# cococartridge.net
KiCad netlist of a schematic drawn in EAGLE
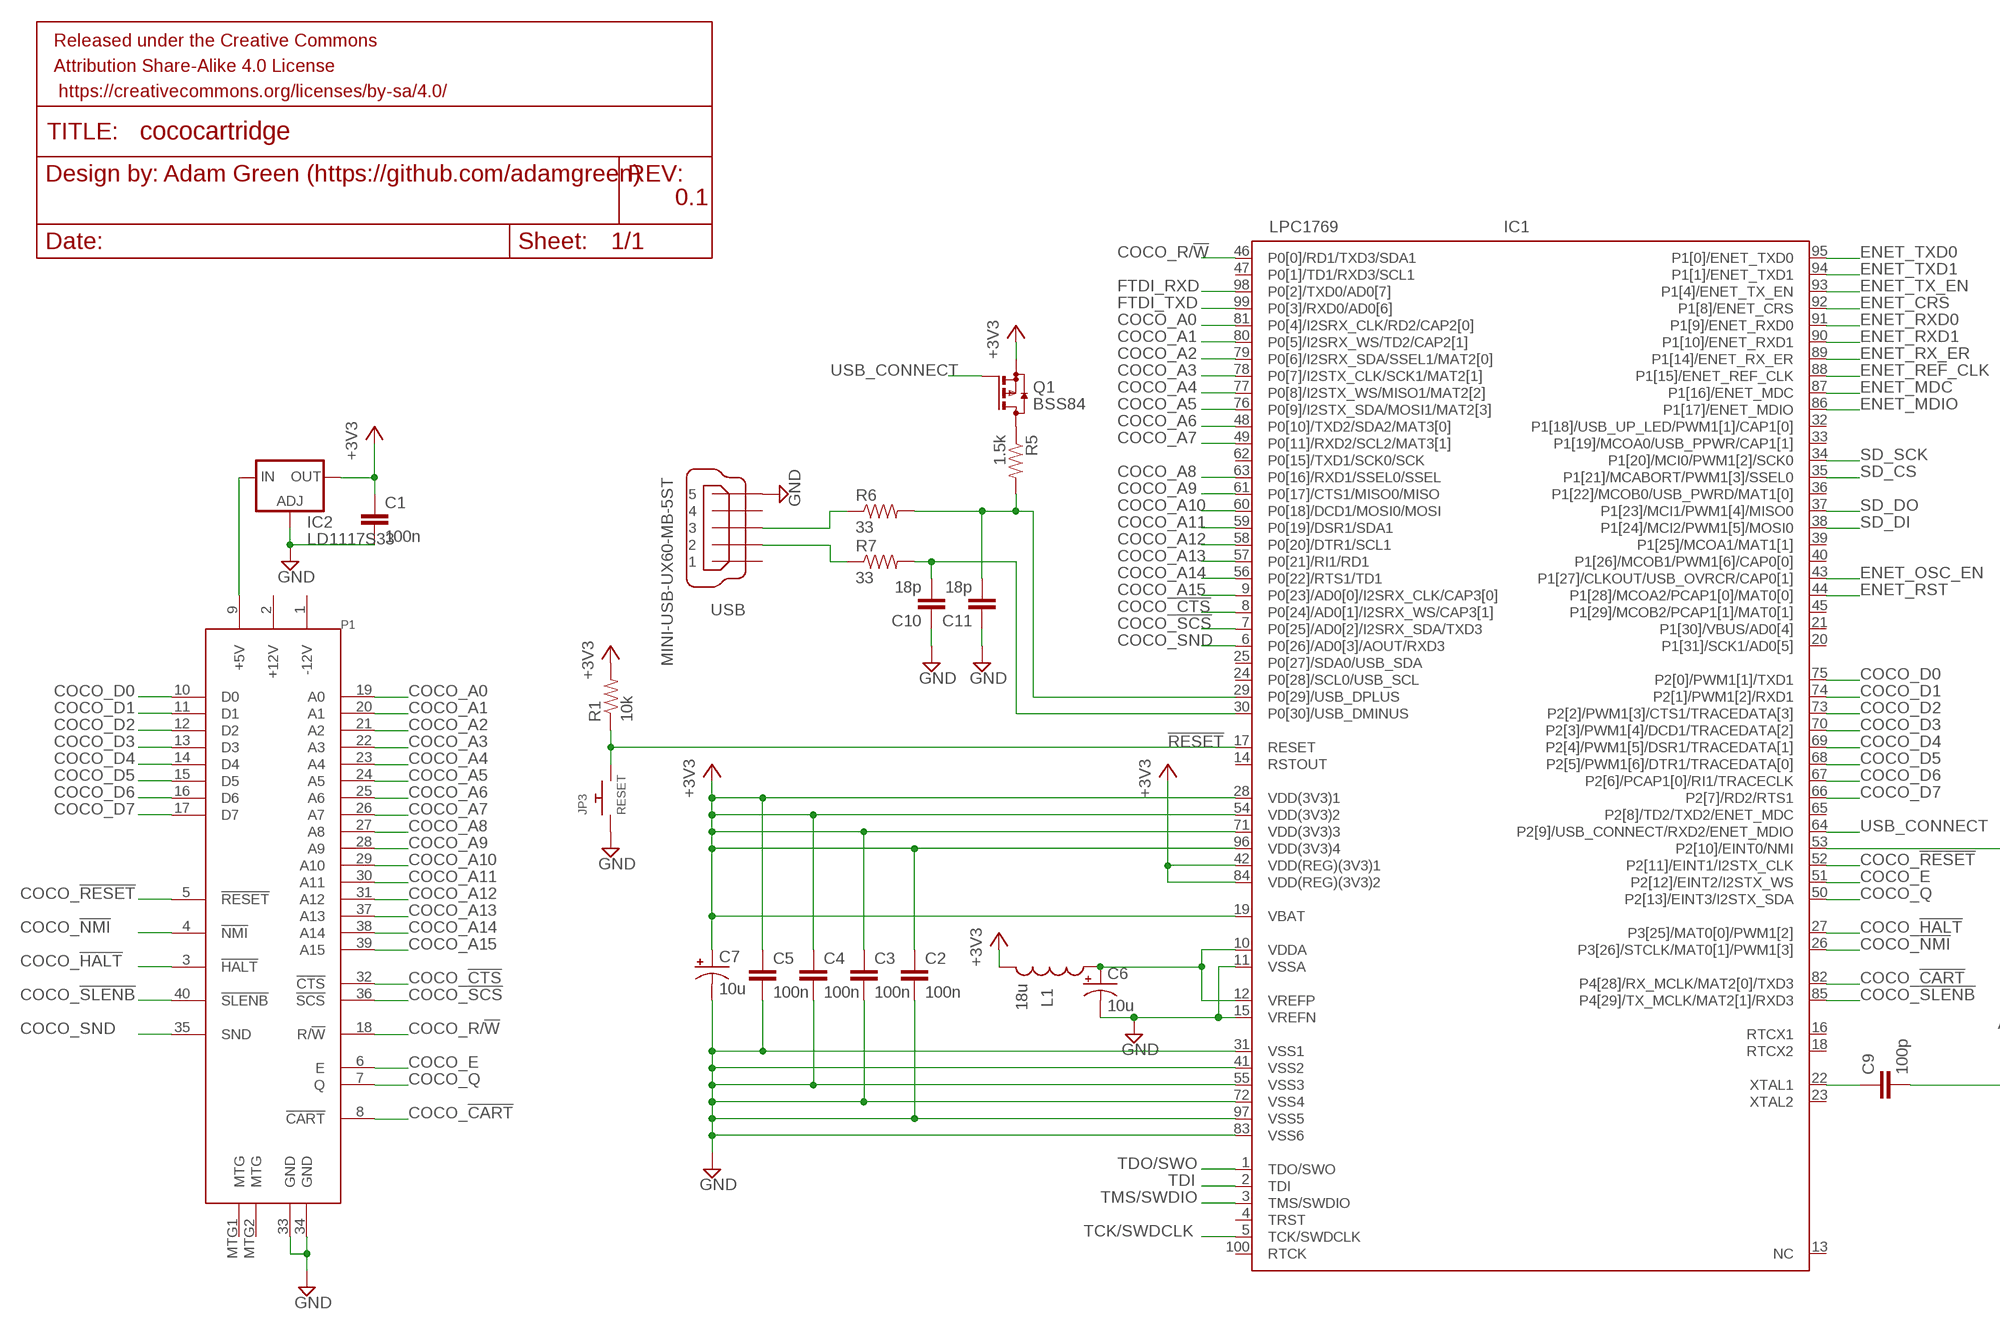
[diagram p0: schematic, sheet 1, part 1 of 2]
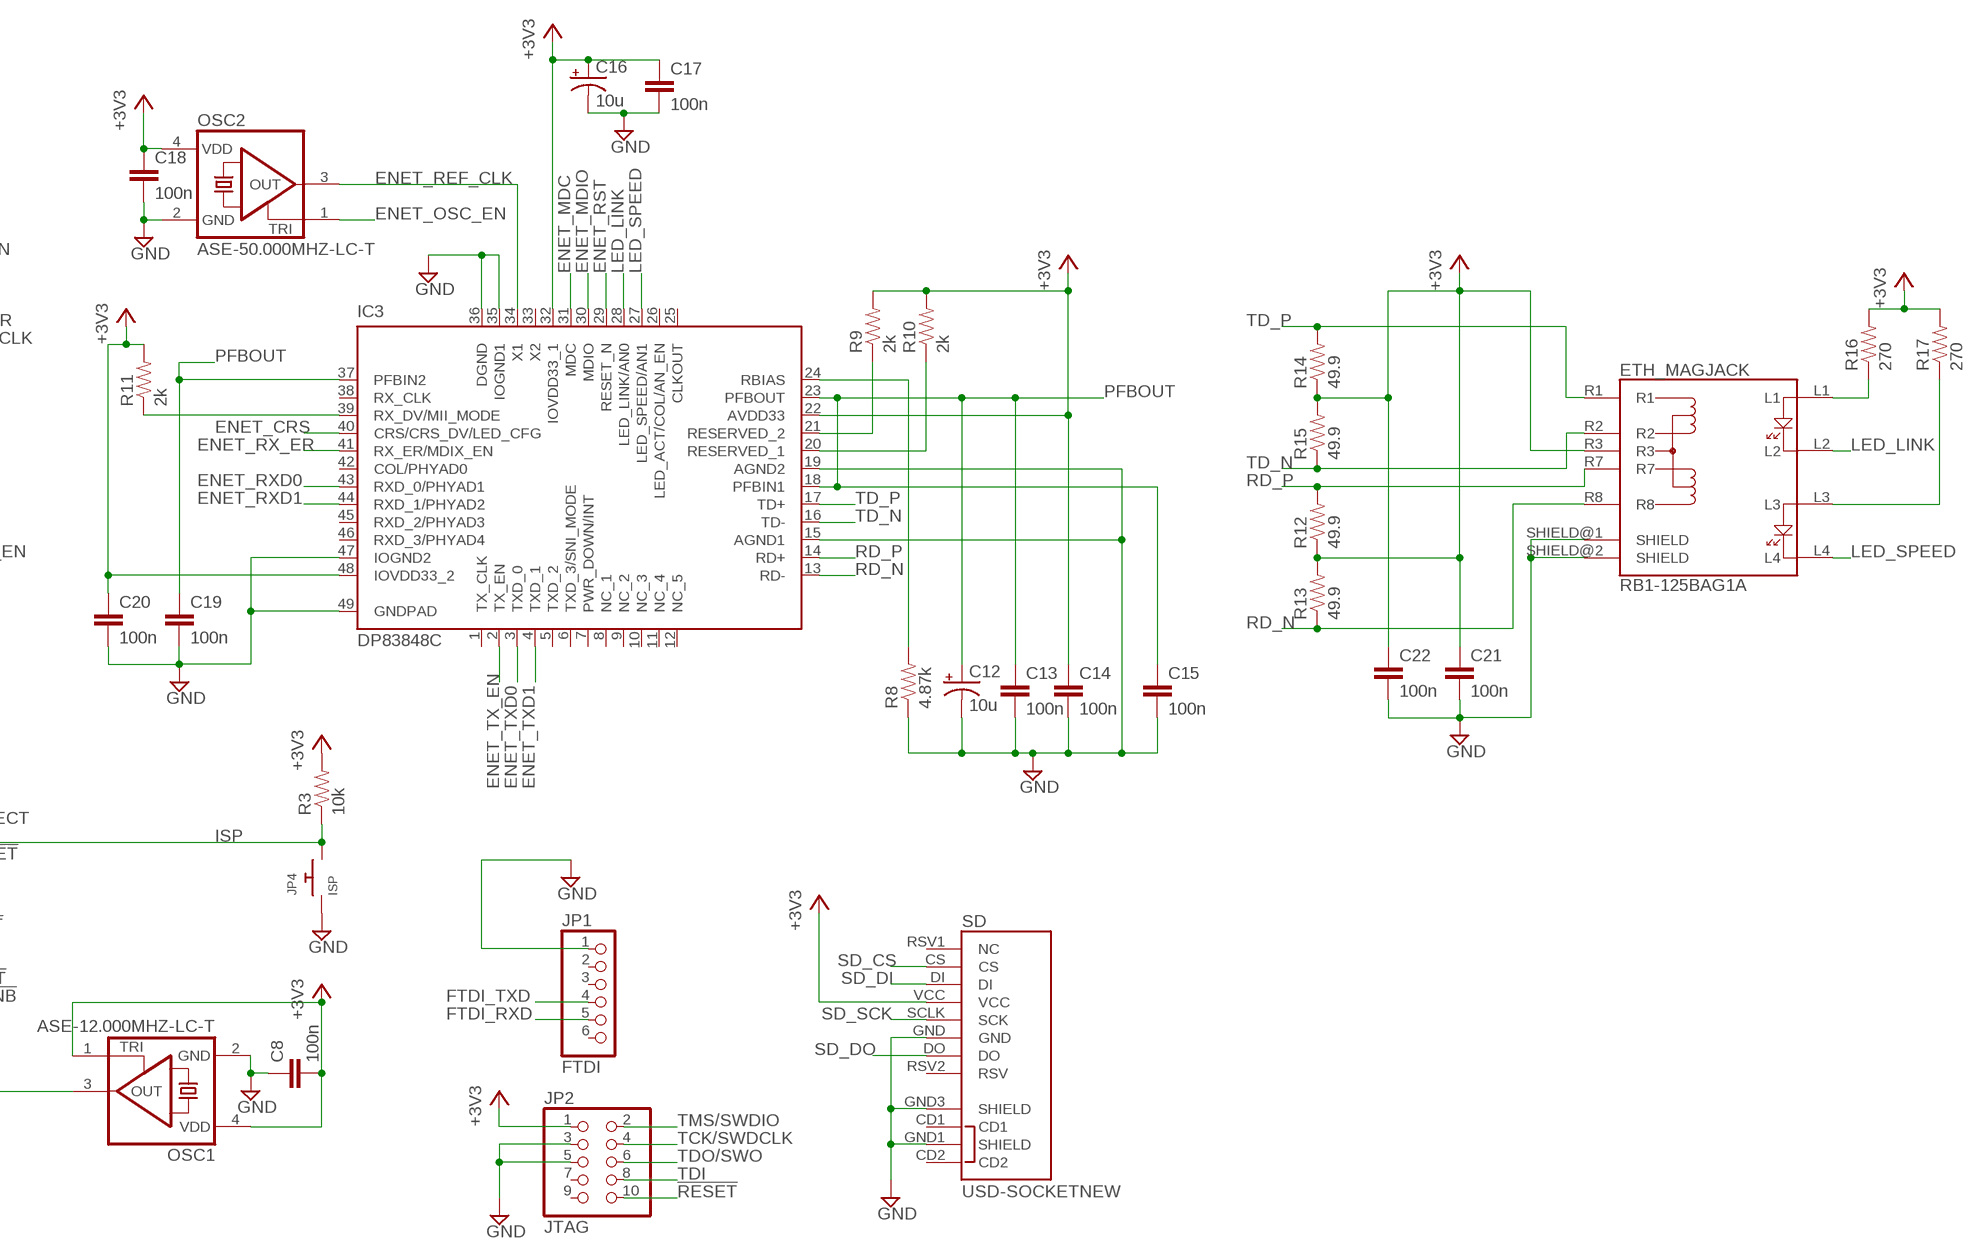
[diagram p1: schematic, sheet 1, part 2 of 2]

(export (version "E")
  (design (tool "Eeschema 10.0.6"))
  (components
    (comp (ref "C1")
      (value "100n")
      (footprint "eagle-import:0805")
      (libsource (lib "eagle-import") (part "CAP0805"))
    )
    (comp (ref "C2")
      (value "100n")
      (footprint "eagle-import:0805")
      (libsource (lib "eagle-import") (part "CAP0805"))
    )
    (comp (ref "C3")
      (value "100n")
      (footprint "eagle-import:0805")
      (libsource (lib "eagle-import") (part "CAP0805"))
    )
    (comp (ref "C4")
      (value "100n")
      (footprint "eagle-import:0805")
      (libsource (lib "eagle-import") (part "CAP0805"))
    )
    (comp (ref "C5")
      (value "100n")
      (footprint "eagle-import:0805")
      (libsource (lib "eagle-import") (part "CAP0805"))
    )
    (comp (ref "C6")
      (value "10u")
      (footprint "eagle-import:EIA3216")
      (libsource (lib "eagle-import") (part "CAP_POL1206"))
    )
    (comp (ref "C7")
      (value "10u")
      (footprint "eagle-import:EIA3216")
      (libsource (lib "eagle-import") (part "CAP_POL1206"))
    )
    (comp (ref "C8")
      (value "100n")
      (footprint "eagle-import:0805")
      (libsource (lib "eagle-import") (part "CAP0805"))
    )
    (comp (ref "C9")
      (value "100p")
      (footprint "eagle-import:0805")
      (libsource (lib "eagle-import") (part "CAP0805"))
    )
    (comp (ref "C10")
      (value "18p")
      (footprint "eagle-import:0805")
      (libsource (lib "eagle-import") (part "CAP0805"))
    )
    (comp (ref "C11")
      (value "18p")
      (footprint "eagle-import:0805")
      (libsource (lib "eagle-import") (part "CAP0805"))
    )
    (comp (ref "C12")
      (value "10u")
      (footprint "eagle-import:EIA3216")
      (libsource (lib "eagle-import") (part "CAP_POL1206"))
    )
    (comp (ref "C13")
      (value "100n")
      (footprint "eagle-import:0805")
      (libsource (lib "eagle-import") (part "CAP0805"))
    )
    (comp (ref "C14")
      (value "100n")
      (footprint "eagle-import:0805")
      (libsource (lib "eagle-import") (part "CAP0805"))
    )
    (comp (ref "C15")
      (value "100n")
      (footprint "eagle-import:0805")
      (libsource (lib "eagle-import") (part "CAP0805"))
    )
    (comp (ref "C16")
      (value "10u")
      (footprint "eagle-import:EIA3216")
      (libsource (lib "eagle-import") (part "CAP_POL1206"))
    )
    (comp (ref "C17")
      (value "100n")
      (footprint "eagle-import:0805")
      (libsource (lib "eagle-import") (part "CAP0805"))
    )
    (comp (ref "C18")
      (value "100n")
      (footprint "eagle-import:0805")
      (libsource (lib "eagle-import") (part "CAP0805"))
    )
    (comp (ref "C19")
      (value "100n")
      (footprint "eagle-import:0805")
      (libsource (lib "eagle-import") (part "CAP0805"))
    )
    (comp (ref "C20")
      (value "100n")
      (footprint "eagle-import:0805")
      (libsource (lib "eagle-import") (part "CAP0805"))
    )
    (comp (ref "C21")
      (value "100n")
      (footprint "eagle-import:0805")
      (libsource (lib "eagle-import") (part "CAP0805"))
    )
    (comp (ref "C22")
      (value "100n")
      (footprint "eagle-import:0805")
      (libsource (lib "eagle-import") (part "CAP0805"))
    )
    (comp (ref "ETH_MAGJACK")
      (value "RB1-125BAG1A")
      (footprint "eagle-import:RB1-125BAG1A")
      (libsource (lib "eagle-import") (part "RB1-125BAG1A"))
    )
    (comp (ref "IC1")
      (value "LPC1769")
      (footprint "eagle-import:LQFP100-14X14")
      (libsource (lib "eagle-import") (part "LPC1769"))
    )
    (comp (ref "IC2")
      (value "LD1117S33")
      (footprint "eagle-import:SOT223")
      (libsource (lib "eagle-import") (part "LD117A?S33TR"))
    )
    (comp (ref "IC3")
      (value "DP83848C")
      (footprint "eagle-import:LQFP48")
      (libsource (lib "eagle-import") (part "DP83848C"))
    )
    (comp (ref "JP1")
      (value "FTDI")
      (footprint "eagle-import:1X06")
      (libsource (lib "eagle-import") (part "PINHD-1X6"))
    )
    (comp (ref "JP2")
      (value "JTAG")
      (footprint "eagle-import:FTSH-105")
      (libsource (lib "eagle-import") (part "FTSH-105"))
    )
    (comp (ref "JP3")
      (value "RESET")
      (footprint "eagle-import:1206")
      (libsource (lib "eagle-import") (part "JUMPER-1206"))
    )
    (comp (ref "JP4")
      (value "ISP")
      (footprint "eagle-import:1206")
      (libsource (lib "eagle-import") (part "JUMPER-1206"))
    )
    (comp (ref "L1")
      (value "18u")
      (footprint "eagle-import:1210")
      (libsource (lib "eagle-import") (part "INDUCTOR1210"))
    )
    (comp (ref "OSC1")
      (value "ASE-12.000MHZ-LC-T")
      (footprint "eagle-import:ASE")
      (libsource (lib "eagle-import") (part "ASE"))
    )
    (comp (ref "OSC2")
      (value "ASE-50.000MHZ-LC-T")
      (footprint "eagle-import:ASE")
      (libsource (lib "eagle-import") (part "ASE"))
    )
    (comp (ref "P1")
      (value "COCO-CART3.5X2.5")
      (footprint "eagle-import:COCO-CART-3.5X2.5")
      (libsource (lib "eagle-import") (part "COCO-CART3.5X2.5"))
    )
    (comp (ref "Q1")
      (value "BSS84")
      (footprint "eagle-import:SOT23")
      (libsource (lib "eagle-import") (part "BSS84"))
    )
    (comp (ref "R1")
      (value "10k")
      (footprint "eagle-import:0805")
      (libsource (lib "eagle-import") (part "RESISTOR0805-RES"))
    )
    (comp (ref "R3")
      (value "10k")
      (footprint "eagle-import:0805")
      (libsource (lib "eagle-import") (part "RESISTOR0805-RES"))
    )
    (comp (ref "R5")
      (value "1.5k")
      (footprint "eagle-import:0805")
      (libsource (lib "eagle-import") (part "RESISTOR0805-RES"))
    )
    (comp (ref "R6")
      (value "33")
      (footprint "eagle-import:0805")
      (libsource (lib "eagle-import") (part "RESISTOR0805-RES"))
    )
    (comp (ref "R7")
      (value "33")
      (footprint "eagle-import:0805")
      (libsource (lib "eagle-import") (part "RESISTOR0805-RES"))
    )
    (comp (ref "R8")
      (value "4.87k")
      (footprint "eagle-import:0805")
      (libsource (lib "eagle-import") (part "RESISTOR0805-RES"))
    )
    (comp (ref "R9")
      (value "2k")
      (footprint "eagle-import:0805")
      (libsource (lib "eagle-import") (part "RESISTOR0805-RES"))
    )
    (comp (ref "R10")
      (value "2k")
      (footprint "eagle-import:0805")
      (libsource (lib "eagle-import") (part "RESISTOR0805-RES"))
    )
    (comp (ref "R11")
      (value "2k")
      (footprint "eagle-import:0805")
      (libsource (lib "eagle-import") (part "RESISTOR0805-RES"))
    )
    (comp (ref "R12")
      (value "49.9")
      (footprint "eagle-import:0805")
      (libsource (lib "eagle-import") (part "RESISTOR0805-RES"))
    )
    (comp (ref "R13")
      (value "49.9")
      (footprint "eagle-import:0805")
      (libsource (lib "eagle-import") (part "RESISTOR0805-RES"))
    )
    (comp (ref "R14")
      (value "49.9")
      (footprint "eagle-import:0805")
      (libsource (lib "eagle-import") (part "RESISTOR0805-RES"))
    )
    (comp (ref "R15")
      (value "49.9")
      (footprint "eagle-import:0805")
      (libsource (lib "eagle-import") (part "RESISTOR0805-RES"))
    )
    (comp (ref "R16")
      (value "270")
      (footprint "eagle-import:0805")
      (libsource (lib "eagle-import") (part "RESISTOR0805-RES"))
    )
    (comp (ref "R17")
      (value "270")
      (footprint "eagle-import:0805")
      (libsource (lib "eagle-import") (part "RESISTOR0805-RES"))
    )
    (comp (ref "SD")
      (value "USD-SOCKETNEW")
      (footprint "eagle-import:MICRO-SD-SOCKET-PP")
      (libsource (lib "eagle-import") (part "USD-SOCKETNEW"))
    )
    (comp (ref "USB")
      (value "MINI-USB-UX60-MB-5ST")
      (footprint "eagle-import:UX60-MB-5ST")
      (libsource (lib "eagle-import") (part "MINI-USB-UX60-MB-5ST"))
    )
  )
  (nets
    (net (code "1") (name "+3V3") (class "Default")
      (node (ref "C1") (pin "1") (pinfunction "1_1") (pintype "passive"))
      (node (ref "C14") (pin "1") (pinfunction "1_1") (pintype "passive"))
      (node (ref "C16") (pin "A") (pinfunction "+_A") (pintype "passive"))
      (node (ref "C17") (pin "1") (pinfunction "1_1") (pintype "passive"))
      (node (ref "C18") (pin "1") (pinfunction "1_1") (pintype "passive"))
      (node (ref "C2") (pin "1") (pinfunction "1_1") (pintype "passive"))
      (node (ref "C20") (pin "1") (pinfunction "1_1") (pintype "passive"))
      (node (ref "C21") (pin "1") (pinfunction "1_1") (pintype "passive"))
      (node (ref "C22") (pin "1") (pinfunction "1_1") (pintype "passive"))
      (node (ref "C3") (pin "1") (pinfunction "1_1") (pintype "passive"))
      (node (ref "C4") (pin "1") (pinfunction "1_1") (pintype "passive"))
      (node (ref "C5") (pin "1") (pinfunction "1_1") (pintype "passive"))
      (node (ref "C7") (pin "A") (pinfunction "+_A") (pintype "passive"))
      (node (ref "C8") (pin "2") (pinfunction "2_2") (pintype "passive"))
      (node (ref "ETH_MAGJACK") (pin "R3") (pinfunction "R3_R3") (pintype "bidirectional"))
      (node (ref "IC1") (pin "19") (pinfunction "VBAT_19") (pintype "bidirectional"))
      (node (ref "IC1") (pin "28") (pinfunction "VDD(3V3)1_28") (pintype "bidirectional"))
      (node (ref "IC1") (pin "42") (pinfunction "VDD(REG)(3V3)1_42") (pintype "bidirectional"))
      (node (ref "IC1") (pin "54") (pinfunction "VDD(3V3)2_54") (pintype "bidirectional"))
      (node (ref "IC1") (pin "71") (pinfunction "VDD(3V3)3_71") (pintype "bidirectional"))
      (node (ref "IC1") (pin "84") (pinfunction "VDD(REG)(3V3)2_84") (pintype "bidirectional"))
      (node (ref "IC1") (pin "96") (pinfunction "VDD(3V3)4_96") (pintype "bidirectional"))
      (node (ref "IC2") (pin "4") (pinfunction "OUT_4") (pintype "passive"))
      (node (ref "IC3") (pin "22") (pinfunction "AVDD33_22") (pintype "power_in"))
      (node (ref "IC3") (pin "32") (pinfunction "IOVDD33_1_32") (pintype "power_in"))
      (node (ref "IC3") (pin "48") (pinfunction "IOVDD33_2_48") (pintype "power_in"))
      (node (ref "JP2") (pin "1") (pinfunction "1_1") (pintype "passive"))
      (node (ref "L1") (pin "2") (pinfunction "2_2") (pintype "passive"))
      (node (ref "OSC1") (pin "1") (pinfunction "TRI_1") (pintype "input"))
      (node (ref "OSC1") (pin "4") (pinfunction "VDD_4") (pintype "power_in"))
      (node (ref "OSC2") (pin "4") (pinfunction "VDD_4") (pintype "power_in"))
      (node (ref "Q1") (pin "2") (pinfunction "S_2") (pintype "passive"))
      (node (ref "R1") (pin "2") (pinfunction "2_2") (pintype "passive"))
      (node (ref "R10") (pin "2") (pinfunction "2_2") (pintype "passive"))
      (node (ref "R11") (pin "2") (pinfunction "2_2") (pintype "passive"))
      (node (ref "R12") (pin "1") (pinfunction "1_1") (pintype "passive"))
      (node (ref "R13") (pin "2") (pinfunction "2_2") (pintype "passive"))
      (node (ref "R14") (pin "1") (pinfunction "1_1") (pintype "passive"))
      (node (ref "R15") (pin "2") (pinfunction "2_2") (pintype "passive"))
      (node (ref "R16") (pin "2") (pinfunction "2_2") (pintype "passive"))
      (node (ref "R17") (pin "2") (pinfunction "2_2") (pintype "passive"))
      (node (ref "R3") (pin "2") (pinfunction "2_2") (pintype "passive"))
      (node (ref "R9") (pin "2") (pinfunction "2_2") (pintype "passive"))
      (node (ref "SD") (pin "VCC") (pinfunction "VCC_VCC") (pintype "bidirectional"))
    )
    (net (code "2") (name "/COCO_A0") (class "Default")
      (node (ref "IC1") (pin "81") (pinfunction "P0[4]/I2SRX_CLK/RD2/CAP2[0]_81") (pintype "bidirectional"))
      (node (ref "P1") (pin "19") (pinfunction "A0_19") (pintype "output"))
    )
    (net (code "3") (name "/COCO_A1") (class "Default")
      (node (ref "IC1") (pin "80") (pinfunction "P0[5]/I2SRX_WS/TD2/CAP2[1]_80") (pintype "bidirectional"))
      (node (ref "P1") (pin "20") (pinfunction "A1_20") (pintype "output"))
    )
    (net (code "4") (name "/COCO_A2") (class "Default")
      (node (ref "IC1") (pin "79") (pinfunction "P0[6]/I2SRX_SDA/SSEL1/MAT2[0]_79") (pintype "bidirectional"))
      (node (ref "P1") (pin "21") (pinfunction "A2_21") (pintype "output"))
    )
    (net (code "5") (name "/COCO_A3") (class "Default")
      (node (ref "IC1") (pin "78") (pinfunction "P0[7]/I2STX_CLK/SCK1/MAT2[1]_78") (pintype "bidirectional"))
      (node (ref "P1") (pin "22") (pinfunction "A3_22") (pintype "output"))
    )
    (net (code "6") (name "/COCO_A4") (class "Default")
      (node (ref "IC1") (pin "77") (pinfunction "P0[8]/I2STX_WS/MISO1/MAT2[2]_77") (pintype "bidirectional"))
      (node (ref "P1") (pin "23") (pinfunction "A4_23") (pintype "output"))
    )
    (net (code "7") (name "/COCO_A5") (class "Default")
      (node (ref "IC1") (pin "76") (pinfunction "P0[9]/I2STX_SDA/MOSI1/MAT2[3]_76") (pintype "bidirectional"))
      (node (ref "P1") (pin "24") (pinfunction "A5_24") (pintype "output"))
    )
    (net (code "8") (name "/COCO_A6") (class "Default")
      (node (ref "IC1") (pin "48") (pinfunction "P0[10]/TXD2/SDA2/MAT3[0]_48") (pintype "bidirectional"))
      (node (ref "P1") (pin "25") (pinfunction "A6_25") (pintype "output"))
    )
    (net (code "9") (name "/COCO_A7") (class "Default")
      (node (ref "IC1") (pin "49") (pinfunction "P0[11]/RXD2/SCL2/MAT3[1]_49") (pintype "bidirectional"))
      (node (ref "P1") (pin "26") (pinfunction "A7_26") (pintype "output"))
    )
    (net (code "10") (name "/COCO_A8") (class "Default")
      (node (ref "IC1") (pin "63") (pinfunction "P0[16]/RXD1/SSEL0/SSEL_63") (pintype "bidirectional"))
      (node (ref "P1") (pin "27") (pinfunction "A8_27") (pintype "output"))
    )
    (net (code "11") (name "/COCO_A9") (class "Default")
      (node (ref "IC1") (pin "61") (pinfunction "P0[17]/CTS1/MISO0/MISO_61") (pintype "bidirectional"))
      (node (ref "P1") (pin "28") (pinfunction "A9_28") (pintype "output"))
    )
    (net (code "12") (name "/COCO_A10") (class "Default")
      (node (ref "IC1") (pin "60") (pinfunction "P0[18]/DCD1/MOSI0/MOSI_60") (pintype "bidirectional"))
      (node (ref "P1") (pin "29") (pinfunction "A10_29") (pintype "output"))
    )
    (net (code "13") (name "/COCO_A11") (class "Default")
      (node (ref "IC1") (pin "59") (pinfunction "P0[19]/DSR1/SDA1_59") (pintype "bidirectional"))
      (node (ref "P1") (pin "30") (pinfunction "A11_30") (pintype "output"))
    )
    (net (code "14") (name "/COCO_A12") (class "Default")
      (node (ref "IC1") (pin "58") (pinfunction "P0[20]/DTR1/SCL1_58") (pintype "bidirectional"))
      (node (ref "P1") (pin "31") (pinfunction "A12_31") (pintype "output"))
    )
    (net (code "15") (name "/COCO_A13") (class "Default")
      (node (ref "IC1") (pin "57") (pinfunction "P0[21]/RI1/RD1_57") (pintype "bidirectional"))
      (node (ref "P1") (pin "37") (pinfunction "A13_37") (pintype "output"))
    )
    (net (code "16") (name "/COCO_A14") (class "Default")
      (node (ref "IC1") (pin "56") (pinfunction "P0[22]/RTS1/TD1_56") (pintype "bidirectional"))
      (node (ref "P1") (pin "38") (pinfunction "A14_38") (pintype "output"))
    )
    (net (code "17") (name "/COCO_A15") (class "Default")
      (node (ref "IC1") (pin "9") (pinfunction "P0[23]/AD0[0]/I2SRX_CLK/CAP3[0]_9") (pintype "bidirectional"))
      (node (ref "P1") (pin "39") (pinfunction "A15_39") (pintype "output"))
    )
    (net (code "18") (name "/COCO_D0") (class "Default")
      (node (ref "IC1") (pin "75") (pinfunction "P2[0]/PWM1[1]/TXD1_75") (pintype "bidirectional"))
      (node (ref "P1") (pin "10") (pinfunction "D0_10") (pintype "bidirectional"))
    )
    (net (code "19") (name "/COCO_D1") (class "Default")
      (node (ref "IC1") (pin "74") (pinfunction "P2[1]/PWM1[2]/RXD1_74") (pintype "bidirectional"))
      (node (ref "P1") (pin "11") (pinfunction "D1_11") (pintype "bidirectional"))
    )
    (net (code "20") (name "/COCO_D2") (class "Default")
      (node (ref "IC1") (pin "73") (pinfunction "P2[2]/PWM1[3]/CTS1/TRACEDATA[3]_73") (pintype "bidirectional"))
      (node (ref "P1") (pin "12") (pinfunction "D2_12") (pintype "bidirectional"))
    )
    (net (code "21") (name "/COCO_D3") (class "Default")
      (node (ref "IC1") (pin "70") (pinfunction "P2[3]/PWM1[4]/DCD1/TRACEDATA[2]_70") (pintype "bidirectional"))
      (node (ref "P1") (pin "13") (pinfunction "D3_13") (pintype "bidirectional"))
    )
    (net (code "22") (name "/COCO_D4") (class "Default")
      (node (ref "IC1") (pin "69") (pinfunction "P2[4]/PWM1[5]/DSR1/TRACEDATA[1]_69") (pintype "bidirectional"))
      (node (ref "P1") (pin "14") (pinfunction "D4_14") (pintype "bidirectional"))
    )
    (net (code "23") (name "/COCO_D5") (class "Default")
      (node (ref "IC1") (pin "68") (pinfunction "P2[5]/PWM1[6]/DTR1/TRACEDATA[0]_68") (pintype "bidirectional"))
      (node (ref "P1") (pin "15") (pinfunction "D5_15") (pintype "bidirectional"))
    )
    (net (code "24") (name "/COCO_D6") (class "Default")
      (node (ref "IC1") (pin "67") (pinfunction "P2[6]/PCAP1[0]/RI1/TRACECLK_67") (pintype "bidirectional"))
      (node (ref "P1") (pin "16") (pinfunction "D6_16") (pintype "bidirectional"))
    )
    (net (code "25") (name "/COCO_D7") (class "Default")
      (node (ref "IC1") (pin "66") (pinfunction "P2[7]/RD2/RTS1_66") (pintype "bidirectional"))
      (node (ref "P1") (pin "17") (pinfunction "D7_17") (pintype "bidirectional"))
    )
    (net (code "26") (name "/COCO_E") (class "Default")
      (node (ref "IC1") (pin "51") (pinfunction "P2[12]/EINT2/I2STX_WS_51") (pintype "bidirectional"))
      (node (ref "P1") (pin "6") (pinfunction "E_6") (pintype "output"))
    )
    (net (code "27") (name "/COCO_Q") (class "Default")
      (node (ref "IC1") (pin "50") (pinfunction "P2[13]/EINT3/I2STX_SDA_50") (pintype "bidirectional"))
      (node (ref "P1") (pin "7") (pinfunction "Q_7") (pintype "output"))
    )
    (net (code "28") (name "/COCO_R{slash}~{W}") (class "Default")
      (node (ref "IC1") (pin "46") (pinfunction "P0[0]/RD1/TXD3/SDA1_46") (pintype "bidirectional"))
      (node (ref "P1") (pin "18") (pinfunction "R/~{W}_18") (pintype "output"))
    )
    (net (code "29") (name "/COCO_SND") (class "Default")
      (node (ref "IC1") (pin "6") (pinfunction "P0[26]/AD0[3]/AOUT/RXD3_6") (pintype "bidirectional"))
      (node (ref "P1") (pin "35") (pinfunction "SND_35") (pintype "bidirectional"))
    )
    (net (code "30") (name "/COCO_~{CART}") (class "Default")
      (node (ref "IC1") (pin "82") (pinfunction "P4[28]/RX_MCLK/MAT2[0]/TXD3_82") (pintype "bidirectional"))
      (node (ref "P1") (pin "8") (pinfunction "~{CART}_8") (pintype "input"))
    )
    (net (code "31") (name "/COCO_~{CTS}") (class "Default")
      (node (ref "IC1") (pin "8") (pinfunction "P0[24]/AD0[1]/I2SRX_WS/CAP3[1]_8") (pintype "bidirectional"))
      (node (ref "P1") (pin "32") (pinfunction "~{CTS}_32") (pintype "output"))
    )
    (net (code "32") (name "/COCO_~{HALT}") (class "Default")
      (node (ref "IC1") (pin "27") (pinfunction "P3[25]/MAT0[0]/PWM1[2]_27") (pintype "bidirectional"))
      (node (ref "P1") (pin "3") (pinfunction "~{HALT}_3") (pintype "bidirectional"))
    )
    (net (code "33") (name "/COCO_~{NMI}") (class "Default")
      (node (ref "IC1") (pin "26") (pinfunction "P3[26]/STCLK/MAT0[1]/PWM1[3]_26") (pintype "bidirectional"))
      (node (ref "P1") (pin "4") (pinfunction "~{NMI}_4") (pintype "bidirectional"))
    )
    (net (code "34") (name "/COCO_~{RESET}") (class "Default")
      (node (ref "IC1") (pin "52") (pinfunction "P2[11]/EINT1/I2STX_CLK_52") (pintype "bidirectional"))
      (node (ref "P1") (pin "5") (pinfunction "~{RESET}_5") (pintype "bidirectional"))
    )
    (net (code "35") (name "/COCO_~{SCS}") (class "Default")
      (node (ref "IC1") (pin "7") (pinfunction "P0[25]/AD0[2]/I2SRX_SDA/TXD3_7") (pintype "bidirectional"))
      (node (ref "P1") (pin "36") (pinfunction "~{SCS}_36") (pintype "output"))
    )
    (net (code "36") (name "/COCO_~{SLENB}") (class "Default")
      (node (ref "IC1") (pin "85") (pinfunction "P4[29]/TX_MCLK/MAT2[1]/RXD3_85") (pintype "bidirectional"))
      (node (ref "P1") (pin "40") (pinfunction "~{SLENB}_40") (pintype "input"))
    )
    (net (code "37") (name "/ENET_CRS") (class "Default")
      (node (ref "IC1") (pin "92") (pinfunction "P1[8]/ENET_CRS_92") (pintype "bidirectional"))
      (node (ref "IC3") (pin "40") (pinfunction "CRS/CRS_DV/LED_CFG_40") (pintype "output"))
    )
    (net (code "38") (name "/ENET_MDC") (class "Default")
      (node (ref "IC1") (pin "87") (pinfunction "P1[16]/ENET_MDC_87") (pintype "bidirectional"))
      (node (ref "IC3") (pin "31") (pinfunction "MDC_31") (pintype "input"))
    )
    (net (code "39") (name "/ENET_MDIO") (class "Default")
      (node (ref "IC1") (pin "86") (pinfunction "P1[17]/ENET_MDIO_86") (pintype "bidirectional"))
      (node (ref "IC3") (pin "30") (pinfunction "MDIO_30") (pintype "bidirectional"))
    )
    (net (code "40") (name "/ENET_OSC_EN") (class "Default")
      (node (ref "IC1") (pin "43") (pinfunction "P1[27]/CLKOUT/USB_OVRCR/CAP0[1]_43") (pintype "bidirectional"))
      (node (ref "OSC2") (pin "1") (pinfunction "TRI_1") (pintype "input"))
    )
    (net (code "41") (name "/ENET_REF_CLK") (class "Default")
      (node (ref "IC1") (pin "88") (pinfunction "P1[15]/ENET_REF_CLK_88") (pintype "bidirectional"))
      (node (ref "IC3") (pin "34") (pinfunction "X1_34") (pintype "input"))
      (node (ref "OSC2") (pin "3") (pinfunction "OUT_3") (pintype "output"))
    )
    (net (code "42") (name "/ENET_RST") (class "Default")
      (node (ref "IC1") (pin "44") (pinfunction "P1[28]/MCOA2/PCAP1[0]/MAT0[0]_44") (pintype "bidirectional"))
      (node (ref "IC3") (pin "29") (pinfunction "RESET_N_29") (pintype "input"))
    )
    (net (code "43") (name "/ENET_RXD0") (class "Default")
      (node (ref "IC1") (pin "91") (pinfunction "P1[9]/ENET_RXD0_91") (pintype "bidirectional"))
      (node (ref "IC3") (pin "43") (pinfunction "RXD_0/PHYAD1_43") (pintype "output"))
    )
    (net (code "44") (name "/ENET_RXD1") (class "Default")
      (node (ref "IC1") (pin "90") (pinfunction "P1[10]/ENET_RXD1_90") (pintype "bidirectional"))
      (node (ref "IC3") (pin "44") (pinfunction "RXD_1/PHYAD2_44") (pintype "output"))
    )
    (net (code "45") (name "/ENET_RX_ER") (class "Default")
      (node (ref "IC1") (pin "89") (pinfunction "P1[14]/ENET_RX_ER_89") (pintype "bidirectional"))
      (node (ref "IC3") (pin "41") (pinfunction "RX_ER/MDIX_EN_41") (pintype "output"))
    )
    (net (code "46") (name "/ENET_TXD0") (class "Default")
      (node (ref "IC1") (pin "95") (pinfunction "P1[0]/ENET_TXD0_95") (pintype "bidirectional"))
      (node (ref "IC3") (pin "3") (pinfunction "TXD_0_3") (pintype "input"))
    )
    (net (code "47") (name "/ENET_TXD1") (class "Default")
      (node (ref "IC1") (pin "94") (pinfunction "P1[1]/ENET_TXD1_94") (pintype "bidirectional"))
      (node (ref "IC3") (pin "4") (pinfunction "TXD_1_4") (pintype "input"))
    )
    (net (code "48") (name "/ENET_TX_EN") (class "Default")
      (node (ref "IC1") (pin "93") (pinfunction "P1[4]/ENET_TX_EN_93") (pintype "bidirectional"))
      (node (ref "IC3") (pin "2") (pinfunction "TX_EN_2") (pintype "input"))
    )
    (net (code "49") (name "/FTDI_RXD") (class "Default")
      (node (ref "IC1") (pin "98") (pinfunction "P0[2]/TXD0/AD0[7]_98") (pintype "bidirectional"))
      (node (ref "JP1") (pin "5") (pinfunction "5_5") (pintype "passive"))
    )
    (net (code "50") (name "/FTDI_TXD") (class "Default")
      (node (ref "IC1") (pin "99") (pinfunction "P0[3]/RXD0/AD0[6]_99") (pintype "bidirectional"))
      (node (ref "JP1") (pin "4") (pinfunction "4_4") (pintype "passive"))
    )
    (net (code "51") (name "/ISP") (class "Default")
      (node (ref "IC1") (pin "53") (pinfunction "P2[10]/EINT0/NMI_53") (pintype "bidirectional"))
      (node (ref "JP4") (pin "2") (pinfunction "P$2_2") (pintype "passive"))
      (node (ref "R3") (pin "1") (pinfunction "1_1") (pintype "passive"))
    )
    (net (code "52") (name "/LED_LINK") (class "Default")
      (node (ref "ETH_MAGJACK") (pin "L2") (pinfunction "L2_L2") (pintype "bidirectional"))
      (node (ref "IC3") (pin "28") (pinfunction "LED_LINK/AN0_28") (pintype "output"))
    )
    (net (code "53") (name "/LED_SPEED") (class "Default")
      (node (ref "ETH_MAGJACK") (pin "L4") (pinfunction "L4_L4") (pintype "bidirectional"))
      (node (ref "IC3") (pin "27") (pinfunction "LED_SPEED/AN1_27") (pintype "output"))
    )
    (net (code "54") (name "/PFBOUT") (class "Default")
      (node (ref "C12") (pin "A") (pinfunction "+_A") (pintype "passive"))
      (node (ref "C13") (pin "1") (pinfunction "1_1") (pintype "passive"))
      (node (ref "C15") (pin "1") (pinfunction "1_1") (pintype "passive"))
      (node (ref "C19") (pin "1") (pinfunction "1_1") (pintype "passive"))
      (node (ref "IC3") (pin "18") (pinfunction "PFBIN1_18") (pintype "input"))
      (node (ref "IC3") (pin "23") (pinfunction "PFBOUT_23") (pintype "output"))
      (node (ref "IC3") (pin "37") (pinfunction "PFBIN2_37") (pintype "input"))
    )
    (net (code "55") (name "/RD_N") (class "Default")
      (node (ref "ETH_MAGJACK") (pin "R8") (pinfunction "R8_R8") (pintype "bidirectional"))
      (node (ref "IC3") (pin "13") (pinfunction "RD-_13") (pintype "bidirectional"))
      (node (ref "R13") (pin "1") (pinfunction "1_1") (pintype "passive"))
    )
    (net (code "56") (name "/RD_P") (class "Default")
      (node (ref "ETH_MAGJACK") (pin "R7") (pinfunction "R7_R7") (pintype "bidirectional"))
      (node (ref "IC3") (pin "14") (pinfunction "RD+_14") (pintype "bidirectional"))
      (node (ref "R12") (pin "2") (pinfunction "2_2") (pintype "passive"))
    )
    (net (code "57") (name "/SD_CS") (class "Default")
      (node (ref "IC1") (pin "35") (pinfunction "P1[21]/MCABORT/PWM1[3]/SSEL0_35") (pintype "bidirectional"))
      (node (ref "SD") (pin "CS") (pinfunction "CS_CS") (pintype "bidirectional"))
    )
    (net (code "58") (name "/SD_DI") (class "Default")
      (node (ref "IC1") (pin "38") (pinfunction "P1[24]/MCI2/PWM1[5]/MOSI0_38") (pintype "bidirectional"))
      (node (ref "SD") (pin "DI") (pinfunction "DI_DI") (pintype "bidirectional"))
    )
    (net (code "59") (name "/SD_DO") (class "Default")
      (node (ref "IC1") (pin "37") (pinfunction "P1[23]/MCI1/PWM1[4]/MISO0_37") (pintype "bidirectional"))
      (node (ref "SD") (pin "DO") (pinfunction "DO_DO") (pintype "bidirectional"))
    )
    (net (code "60") (name "/SD_SCK") (class "Default")
      (node (ref "IC1") (pin "34") (pinfunction "P1[20]/MCI0/PWM1[2]/SCK0_34") (pintype "bidirectional"))
      (node (ref "SD") (pin "SCLK") (pinfunction "SCK_SCLK") (pintype "bidirectional"))
    )
    (net (code "61") (name "/TCK{slash}SWDCLK") (class "Default")
      (node (ref "IC1") (pin "5") (pinfunction "TCK/SWDCLK_5") (pintype "bidirectional"))
      (node (ref "JP2") (pin "4") (pinfunction "4_4") (pintype "passive"))
    )
    (net (code "62") (name "/TDI") (class "Default")
      (node (ref "IC1") (pin "2") (pinfunction "TDI_2") (pintype "bidirectional"))
      (node (ref "JP2") (pin "8") (pinfunction "8_8") (pintype "passive"))
    )
    (net (code "63") (name "/TDO{slash}SWO") (class "Default")
      (node (ref "IC1") (pin "1") (pinfunction "TDO/SWO_1") (pintype "bidirectional"))
      (node (ref "JP2") (pin "6") (pinfunction "6_6") (pintype "passive"))
    )
    (net (code "64") (name "/TD_N") (class "Default")
      (node (ref "ETH_MAGJACK") (pin "R2") (pinfunction "R2_R2") (pintype "bidirectional"))
      (node (ref "IC3") (pin "16") (pinfunction "TD-_16") (pintype "bidirectional"))
      (node (ref "R15") (pin "1") (pinfunction "1_1") (pintype "passive"))
    )
    (net (code "65") (name "/TD_P") (class "Default")
      (node (ref "ETH_MAGJACK") (pin "R1") (pinfunction "R1_R1") (pintype "bidirectional"))
      (node (ref "IC3") (pin "17") (pinfunction "TD+_17") (pintype "bidirectional"))
      (node (ref "R14") (pin "2") (pinfunction "2_2") (pintype "passive"))
    )
    (net (code "66") (name "/TMS{slash}SWDIO") (class "Default")
      (node (ref "IC1") (pin "3") (pinfunction "TMS/SWDIO_3") (pintype "bidirectional"))
      (node (ref "JP2") (pin "2") (pinfunction "2_2") (pintype "passive"))
    )
    (net (code "67") (name "/USB_CONNECT") (class "Default")
      (node (ref "IC1") (pin "64") (pinfunction "P2[9]/USB_CONNECT/RXD2/ENET_MDIO_64") (pintype "bidirectional"))
      (node (ref "Q1") (pin "1") (pinfunction "G_1") (pintype "passive"))
    )
    (net (code "68") (name "/~{RESET}") (class "Default")
      (node (ref "IC1") (pin "17") (pinfunction "RESET_17") (pintype "bidirectional"))
      (node (ref "JP2") (pin "10") (pinfunction "10_10") (pintype "passive"))
      (node (ref "JP3") (pin "2") (pinfunction "P$2_2") (pintype "passive"))
      (node (ref "R1") (pin "1") (pinfunction "1_1") (pintype "passive"))
    )
    (net (code "69") (name "GND") (class "Default")
      (node (ref "C1") (pin "2") (pinfunction "2_2") (pintype "passive"))
      (node (ref "C10") (pin "1") (pinfunction "1_1") (pintype "passive"))
      (node (ref "C11") (pin "1") (pinfunction "1_1") (pintype "passive"))
      (node (ref "C12") (pin "C") (pinfunction "-_C") (pintype "passive"))
      (node (ref "C13") (pin "2") (pinfunction "2_2") (pintype "passive"))
      (node (ref "C14") (pin "2") (pinfunction "2_2") (pintype "passive"))
      (node (ref "C15") (pin "2") (pinfunction "2_2") (pintype "passive"))
      (node (ref "C16") (pin "C") (pinfunction "-_C") (pintype "passive"))
      (node (ref "C17") (pin "2") (pinfunction "2_2") (pintype "passive"))
      (node (ref "C18") (pin "2") (pinfunction "2_2") (pintype "passive"))
      (node (ref "C19") (pin "2") (pinfunction "2_2") (pintype "passive"))
      (node (ref "C2") (pin "2") (pinfunction "2_2") (pintype "passive"))
      (node (ref "C20") (pin "2") (pinfunction "2_2") (pintype "passive"))
      (node (ref "C21") (pin "2") (pinfunction "2_2") (pintype "passive"))
      (node (ref "C22") (pin "2") (pinfunction "2_2") (pintype "passive"))
      (node (ref "C3") (pin "2") (pinfunction "2_2") (pintype "passive"))
      (node (ref "C4") (pin "2") (pinfunction "2_2") (pintype "passive"))
      (node (ref "C5") (pin "2") (pinfunction "2_2") (pintype "passive"))
      (node (ref "C6") (pin "C") (pinfunction "-_C") (pintype "passive"))
      (node (ref "C7") (pin "C") (pinfunction "-_C") (pintype "passive"))
      (node (ref "C8") (pin "1") (pinfunction "1_1") (pintype "passive"))
      (node (ref "ETH_MAGJACK") (pin "SHIELD@1") (pinfunction "SHIELD_SHIELD@1") (pintype "bidirectional"))
      (node (ref "ETH_MAGJACK") (pin "SHIELD@2") (pinfunction "SHIELD_SHIELD@2") (pintype "bidirectional"))
      (node (ref "IC1") (pin "11") (pinfunction "VSSA_11") (pintype "bidirectional"))
      (node (ref "IC1") (pin "15") (pinfunction "VREFN_15") (pintype "bidirectional"))
      (node (ref "IC1") (pin "31") (pinfunction "VSS1_31") (pintype "bidirectional"))
      (node (ref "IC1") (pin "41") (pinfunction "VSS2_41") (pintype "bidirectional"))
      (node (ref "IC1") (pin "55") (pinfunction "VSS3_55") (pintype "bidirectional"))
      (node (ref "IC1") (pin "72") (pinfunction "VSS4_72") (pintype "bidirectional"))
      (node (ref "IC1") (pin "83") (pinfunction "VSS6_83") (pintype "bidirectional"))
      (node (ref "IC1") (pin "97") (pinfunction "VSS5_97") (pintype "bidirectional"))
      (node (ref "IC2") (pin "1") (pinfunction "ADJ_1") (pintype "input"))
      (node (ref "IC3") (pin "15") (pinfunction "AGND1_15") (pintype "power_in"))
      (node (ref "IC3") (pin "19") (pinfunction "AGND2_19") (pintype "power_in"))
      (node (ref "IC3") (pin "35") (pinfunction "IOGND1_35") (pintype "power_in"))
      (node (ref "IC3") (pin "36") (pinfunction "DGND_36") (pintype "power_in"))
      (node (ref "IC3") (pin "47") (pinfunction "IOGND2_47") (pintype "power_in"))
      (node (ref "IC3") (pin "49") (pinfunction "GNDPAD_49") (pintype "power_in"))
      (node (ref "JP1") (pin "1") (pinfunction "1_1") (pintype "passive"))
      (node (ref "JP2") (pin "3") (pinfunction "3_3") (pintype "passive"))
      (node (ref "JP2") (pin "5") (pinfunction "5_5") (pintype "passive"))
      (node (ref "JP3") (pin "1") (pinfunction "P$1_1") (pintype "passive"))
      (node (ref "JP4") (pin "1") (pinfunction "P$1_1") (pintype "passive"))
      (node (ref "OSC1") (pin "2") (pinfunction "GND_2") (pintype "power_in"))
      (node (ref "OSC2") (pin "2") (pinfunction "GND_2") (pintype "power_in"))
      (node (ref "P1") (pin "33") (pinfunction "GND_33") (pintype "passive"))
      (node (ref "P1") (pin "34") (pinfunction "GND_34") (pintype "passive"))
      (node (ref "R8") (pin "1") (pinfunction "1_1") (pintype "passive"))
      (node (ref "SD") (pin "GND") (pinfunction "GND_GND") (pintype "bidirectional"))
      (node (ref "SD") (pin "GND1") (pinfunction "SHIELD_GND1") (pintype "bidirectional"))
      (node (ref "SD") (pin "GND3") (pinfunction "SHIELD_GND3") (pintype "bidirectional"))
      (node (ref "USB") (pin "5") (pinfunction "5_5") (pintype "input"))
    )
    (net (code "70") (name "Net-(C6-+)") (class "Default")
      (node (ref "C6") (pin "A") (pinfunction "+_A") (pintype "passive"))
      (node (ref "IC1") (pin "10") (pinfunction "VDDA_10") (pintype "bidirectional"))
      (node (ref "IC1") (pin "12") (pinfunction "VREFP_12") (pintype "bidirectional"))
      (node (ref "L1") (pin "1") (pinfunction "1_1") (pintype "passive"))
    )
    (net (code "71") (name "Net-(ETH_MAGJACK-PadL1)") (class "Default")
      (node (ref "ETH_MAGJACK") (pin "L1") (pinfunction "L1_L1") (pintype "bidirectional"))
      (node (ref "R16") (pin "1") (pinfunction "1_1") (pintype "passive"))
    )
    (net (code "72") (name "Net-(ETH_MAGJACK-PadL3)") (class "Default")
      (node (ref "ETH_MAGJACK") (pin "L3") (pinfunction "L3_L3") (pintype "bidirectional"))
      (node (ref "R17") (pin "1") (pinfunction "1_1") (pintype "passive"))
    )
    (net (code "73") (name "Net-(IC1-P0[29]{slash}USB_DPLUS)") (class "Default")
      (node (ref "C11") (pin "2") (pinfunction "2_2") (pintype "passive"))
      (node (ref "IC1") (pin "29") (pinfunction "P0[29]/USB_DPLUS_29") (pintype "bidirectional"))
      (node (ref "R5") (pin "2") (pinfunction "2_2") (pintype "passive"))
      (node (ref "R6") (pin "2") (pinfunction "2_2") (pintype "passive"))
    )
    (net (code "74") (name "Net-(IC1-P0[30]{slash}USB_DMINUS)") (class "Default")
      (node (ref "C10") (pin "2") (pinfunction "2_2") (pintype "passive"))
      (node (ref "IC1") (pin "30") (pinfunction "P0[30]/USB_DMINUS_30") (pintype "bidirectional"))
      (node (ref "R7") (pin "2") (pinfunction "2_2") (pintype "passive"))
    )
    (net (code "75") (name "Net-(IC1-XTAL1)") (class "Default")
      (node (ref "C9") (pin "1") (pinfunction "1_1") (pintype "passive"))
      (node (ref "IC1") (pin "22") (pinfunction "XTAL1_22") (pintype "bidirectional"))
    )
    (net (code "76") (name "Net-(IC2-IN)") (class "Default")
      (node (ref "IC2") (pin "3") (pinfunction "IN_3") (pintype "input"))
      (node (ref "P1") (pin "9") (pinfunction "+5V_9") (pintype "passive"))
    )
    (net (code "77") (name "Net-(IC3-RBIAS)") (class "Default")
      (node (ref "IC3") (pin "24") (pinfunction "RBIAS_24") (pintype "input"))
      (node (ref "R8") (pin "2") (pinfunction "2_2") (pintype "passive"))
    )
    (net (code "78") (name "Net-(IC3-RESERVED_1)") (class "Default")
      (node (ref "IC3") (pin "20") (pinfunction "RESERVED_1_20") (pintype "bidirectional"))
      (node (ref "R10") (pin "1") (pinfunction "1_1") (pintype "passive"))
    )
    (net (code "79") (name "Net-(IC3-RESERVED_2)") (class "Default")
      (node (ref "IC3") (pin "21") (pinfunction "RESERVED_2_21") (pintype "bidirectional"))
      (node (ref "R9") (pin "1") (pinfunction "1_1") (pintype "passive"))
    )
    (net (code "80") (name "Net-(IC3-RX_DV{slash}MII_MODE)") (class "Default")
      (node (ref "IC3") (pin "39") (pinfunction "RX_DV/MII_MODE_39") (pintype "output"))
      (node (ref "R11") (pin "1") (pinfunction "1_1") (pintype "passive"))
    )
    (net (code "81") (name "Net-(OSC1-OUT)") (class "Default")
      (node (ref "C9") (pin "2") (pinfunction "2_2") (pintype "passive"))
      (node (ref "OSC1") (pin "3") (pinfunction "OUT_3") (pintype "output"))
    )
    (net (code "82") (name "Net-(Q1-D)") (class "Default")
      (node (ref "Q1") (pin "3") (pinfunction "D_3") (pintype "passive"))
      (node (ref "R5") (pin "1") (pinfunction "1_1") (pintype "passive"))
    )
    (net (code "83") (name "Net-(R6-Pad1)") (class "Default")
      (node (ref "R6") (pin "1") (pinfunction "1_1") (pintype "passive"))
      (node (ref "USB") (pin "3") (pinfunction "3_3") (pintype "input"))
    )
    (net (code "84") (name "Net-(R7-Pad1)") (class "Default")
      (node (ref "R7") (pin "1") (pinfunction "1_1") (pintype "passive"))
      (node (ref "USB") (pin "2") (pinfunction "2_2") (pintype "input"))
    )
    (net (code "85") (name "unconnected-(IC1-NC-Pad13)") (class "Default")
      (node (ref "IC1") (pin "13") (pinfunction "NC_13") (pintype "bidirectional"))
    )
    (net (code "86") (name "unconnected-(IC1-P0[1]{slash}TD1{slash}RXD3{slash}SCL1-Pad47)") (class "Default")
      (node (ref "IC1") (pin "47") (pinfunction "P0[1]/TD1/RXD3/SCL1_47") (pintype "bidirectional"))
    )
    (net (code "87") (name "unconnected-(IC1-P0[15]{slash}TXD1{slash}SCK0{slash}SCK-Pad62)") (class "Default")
      (node (ref "IC1") (pin "62") (pinfunction "P0[15]/TXD1/SCK0/SCK_62") (pintype "bidirectional"))
    )
    (net (code "88") (name "unconnected-(IC1-P0[27]{slash}SDA0{slash}USB_SDA-Pad25)") (class "Default")
      (node (ref "IC1") (pin "25") (pinfunction "P0[27]/SDA0/USB_SDA_25") (pintype "bidirectional"))
    )
    (net (code "89") (name "unconnected-(IC1-P0[28]{slash}SCL0{slash}USB_SCL-Pad24)") (class "Default")
      (node (ref "IC1") (pin "24") (pinfunction "P0[28]/SCL0/USB_SCL_24") (pintype "bidirectional"))
    )
    (net (code "90") (name "unconnected-(IC1-P1[18]{slash}USB_UP_LED{slash}PWM1[1]{slash}CAP1[0]-Pad32)") (class "Default")
      (node (ref "IC1") (pin "32") (pinfunction "P1[18]/USB_UP_LED/PWM1[1]/CAP1[0]_32") (pintype "bidirectional"))
    )
    (net (code "91") (name "unconnected-(IC1-P1[19]{slash}MCOA0{slash}USB_PPWR{slash}CAP1[1]-Pad33)") (class "Default")
      (node (ref "IC1") (pin "33") (pinfunction "P1[19]/MCOA0/USB_PPWR/CAP1[1]_33") (pintype "bidirectional"))
    )
    (net (code "92") (name "unconnected-(IC1-P1[22]{slash}MCOB0{slash}USB_PWRD{slash}MAT1[0]-Pad36)") (class "Default")
      (node (ref "IC1") (pin "36") (pinfunction "P1[22]/MCOB0/USB_PWRD/MAT1[0]_36") (pintype "bidirectional"))
    )
    (net (code "93") (name "unconnected-(IC1-P1[25]{slash}MCOA1{slash}MAT1[1]-Pad39)") (class "Default")
      (node (ref "IC1") (pin "39") (pinfunction "P1[25]/MCOA1/MAT1[1]_39") (pintype "bidirectional"))
    )
    (net (code "94") (name "unconnected-(IC1-P1[26]{slash}MCOB1{slash}PWM1[6]{slash}CAP0[0]-Pad40)") (class "Default")
      (node (ref "IC1") (pin "40") (pinfunction "P1[26]/MCOB1/PWM1[6]/CAP0[0]_40") (pintype "bidirectional"))
    )
    (net (code "95") (name "unconnected-(IC1-P1[29]{slash}MCOB2{slash}PCAP1[1]{slash}MAT0[1]-Pad45)") (class "Default")
      (node (ref "IC1") (pin "45") (pinfunction "P1[29]/MCOB2/PCAP1[1]/MAT0[1]_45") (pintype "bidirectional"))
    )
    (net (code "96") (name "unconnected-(IC1-P1[30]{slash}VBUS{slash}AD0[4]-Pad21)") (class "Default")
      (node (ref "IC1") (pin "21") (pinfunction "P1[30]/VBUS/AD0[4]_21") (pintype "bidirectional"))
    )
    (net (code "97") (name "unconnected-(IC1-P1[31]{slash}SCK1{slash}AD0[5]-Pad20)") (class "Default")
      (node (ref "IC1") (pin "20") (pinfunction "P1[31]/SCK1/AD0[5]_20") (pintype "bidirectional"))
    )
    (net (code "98") (name "unconnected-(IC1-P2[8]{slash}TD2{slash}TXD2{slash}ENET_MDC-Pad65)") (class "Default")
      (node (ref "IC1") (pin "65") (pinfunction "P2[8]/TD2/TXD2/ENET_MDC_65") (pintype "bidirectional"))
    )
    (net (code "99") (name "unconnected-(IC1-RSTOUT-Pad14)") (class "Default")
      (node (ref "IC1") (pin "14") (pinfunction "RSTOUT_14") (pintype "bidirectional"))
    )
    (net (code "100") (name "unconnected-(IC1-RTCK-Pad100)") (class "Default")
      (node (ref "IC1") (pin "100") (pinfunction "RTCK_100") (pintype "bidirectional"))
    )
    (net (code "101") (name "unconnected-(IC1-RTCX1-Pad16)") (class "Default")
      (node (ref "IC1") (pin "16") (pinfunction "RTCX1_16") (pintype "bidirectional"))
    )
    (net (code "102") (name "unconnected-(IC1-RTCX2-Pad18)") (class "Default")
      (node (ref "IC1") (pin "18") (pinfunction "RTCX2_18") (pintype "bidirectional"))
    )
    (net (code "103") (name "unconnected-(IC1-TRST-Pad4)") (class "Default")
      (node (ref "IC1") (pin "4") (pinfunction "TRST_4") (pintype "bidirectional"))
    )
    (net (code "104") (name "unconnected-(IC1-XTAL2-Pad23)") (class "Default")
      (node (ref "IC1") (pin "23") (pinfunction "XTAL2_23") (pintype "bidirectional"))
    )
    (net (code "105") (name "unconnected-(IC3-CLKOUT-Pad25)") (class "Default")
      (node (ref "IC3") (pin "25") (pinfunction "CLKOUT_25") (pintype "output"))
    )
    (net (code "106") (name "unconnected-(IC3-COL{slash}PHYAD0-Pad42)") (class "Default")
      (node (ref "IC3") (pin "42") (pinfunction "COL/PHYAD0_42") (pintype "output"))
    )
    (net (code "107") (name "unconnected-(IC3-LED_ACT{slash}COL{slash}AN_EN-Pad26)") (class "Default")
      (node (ref "IC3") (pin "26") (pinfunction "LED_ACT/COL/AN_EN_26") (pintype "output"))
    )
    (net (code "108") (name "unconnected-(IC3-NC_1-Pad8)") (class "Default")
      (node (ref "IC3") (pin "8") (pinfunction "NC_1_8") (pintype "no_connect"))
    )
    (net (code "109") (name "unconnected-(IC3-NC_2-Pad9)") (class "Default")
      (node (ref "IC3") (pin "9") (pinfunction "NC_2_9") (pintype "no_connect"))
    )
    (net (code "110") (name "unconnected-(IC3-NC_3-Pad10)") (class "Default")
      (node (ref "IC3") (pin "10") (pinfunction "NC_3_10") (pintype "no_connect"))
    )
    (net (code "111") (name "unconnected-(IC3-NC_4-Pad11)") (class "Default")
      (node (ref "IC3") (pin "11") (pinfunction "NC_4_11") (pintype "no_connect"))
    )
    (net (code "112") (name "unconnected-(IC3-NC_5-Pad12)") (class "Default")
      (node (ref "IC3") (pin "12") (pinfunction "NC_5_12") (pintype "no_connect"))
    )
    (net (code "113") (name "unconnected-(IC3-PWR_DOWN{slash}INT-Pad7)") (class "Default")
      (node (ref "IC3") (pin "7") (pinfunction "PWR_DOWN/INT_7") (pintype "input"))
    )
    (net (code "114") (name "unconnected-(IC3-RXD_2{slash}PHYAD3-Pad45)") (class "Default")
      (node (ref "IC3") (pin "45") (pinfunction "RXD_2/PHYAD3_45") (pintype "output"))
    )
    (net (code "115") (name "unconnected-(IC3-RXD_3{slash}PHYAD4-Pad46)") (class "Default")
      (node (ref "IC3") (pin "46") (pinfunction "RXD_3/PHYAD4_46") (pintype "output"))
    )
    (net (code "116") (name "unconnected-(IC3-RX_CLK-Pad38)") (class "Default")
      (node (ref "IC3") (pin "38") (pinfunction "RX_CLK_38") (pintype "output"))
    )
    (net (code "117") (name "unconnected-(IC3-TXD_2-Pad5)") (class "Default")
      (node (ref "IC3") (pin "5") (pinfunction "TXD_2_5") (pintype "input"))
    )
    (net (code "118") (name "unconnected-(IC3-TXD_3{slash}SNI_MODE-Pad6)") (class "Default")
      (node (ref "IC3") (pin "6") (pinfunction "TXD_3/SNI_MODE_6") (pintype "input"))
    )
    (net (code "119") (name "unconnected-(IC3-TX_CLK-Pad1)") (class "Default")
      (node (ref "IC3") (pin "1") (pinfunction "TX_CLK_1") (pintype "output"))
    )
    (net (code "120") (name "unconnected-(IC3-X2-Pad33)") (class "Default")
      (node (ref "IC3") (pin "33") (pinfunction "X2_33") (pintype "output"))
    )
    (net (code "121") (name "unconnected-(JP1-Pad2)") (class "Default")
      (node (ref "JP1") (pin "2") (pinfunction "2_2") (pintype "passive"))
    )
    (net (code "122") (name "unconnected-(JP1-Pad3)") (class "Default")
      (node (ref "JP1") (pin "3") (pinfunction "3_3") (pintype "passive"))
    )
    (net (code "123") (name "unconnected-(JP1-Pad6)") (class "Default")
      (node (ref "JP1") (pin "6") (pinfunction "6_6") (pintype "passive"))
    )
    (net (code "124") (name "unconnected-(JP2-Pad7)") (class "Default")
      (node (ref "JP2") (pin "7") (pinfunction "7_7") (pintype "passive"))
    )
    (net (code "125") (name "unconnected-(JP2-Pad9)") (class "Default")
      (node (ref "JP2") (pin "9") (pinfunction "9_9") (pintype "passive"))
    )
    (net (code "126") (name "unconnected-(P1-+12V-Pad2)") (class "Default")
      (node (ref "P1") (pin "2") (pinfunction "+12V_2") (pintype "passive"))
    )
    (net (code "127") (name "unconnected-(P1--12V-Pad1)") (class "Default")
      (node (ref "P1") (pin "1") (pinfunction "-12V_1") (pintype "passive"))
    )
    (net (code "128") (name "unconnected-(P1-MTG-PadMTG1)") (class "Default")
      (node (ref "P1") (pin "MTG1") (pinfunction "MTG_MTG1") (pintype "passive"))
    )
    (net (code "129") (name "unconnected-(P1-MTG-PadMTG2)") (class "Default")
      (node (ref "P1") (pin "MTG2") (pinfunction "MTG_MTG2") (pintype "passive"))
    )
    (net (code "130") (name "unconnected-(SD-NC-PadRSV1)") (class "Default")
      (node (ref "SD") (pin "RSV1") (pinfunction "NC_RSV1") (pintype "bidirectional"))
    )
    (net (code "131") (name "unconnected-(SD-PadCD1)") (class "Default")
      (node (ref "SD") (pin "CD1") (pinfunction "CD1_CD1") (pintype "bidirectional"))
    )
    (net (code "132") (name "unconnected-(SD-PadCD2)") (class "Default")
      (node (ref "SD") (pin "CD2") (pinfunction "CD2_CD2") (pintype "bidirectional"))
    )
    (net (code "133") (name "unconnected-(SD-RSV-PadRSV2)") (class "Default")
      (node (ref "SD") (pin "RSV2") (pinfunction "RSV_RSV2") (pintype "bidirectional"))
    )
    (net (code "134") (name "unconnected-(USB-Pad1)") (class "Default")
      (node (ref "USB") (pin "1") (pinfunction "1_1") (pintype "input"))
    )
    (net (code "135") (name "unconnected-(USB-Pad4)") (class "Default")
      (node (ref "USB") (pin "4") (pinfunction "4_4") (pintype "input"))
    )
  )
)
